# HEART_RATE.net
KiCad netlist of a schematic drawn in Altium Designer
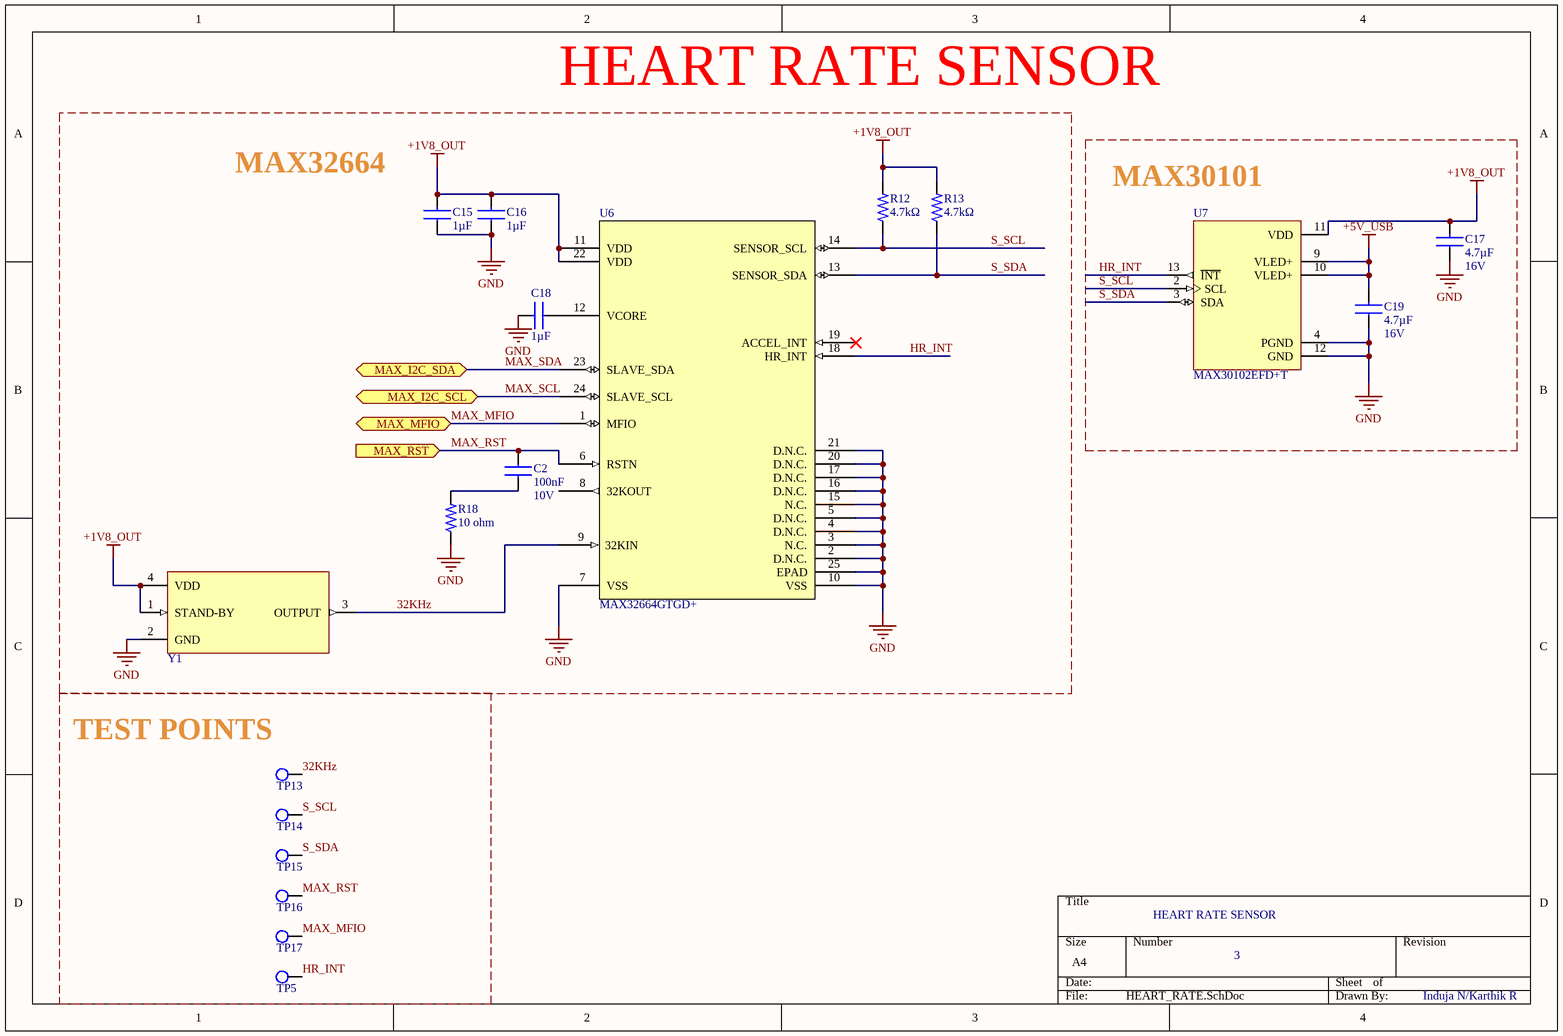
[diagram p0: HEART_RATE.SchDoc]

(export (version "E")
  (design (tool "Eeschema 10.0.6"))
  (components
    (comp (ref "C2")
      (value "100nF")
      (footprint "CAP_0603_1MM")
      (description "0603 0.1 uF 10 V ±10% Tolerance X7R SMT Multilayer Ceramic Chip Capacitor")
      (fields
        (field (name "MANUFACTURER") "Vishay")
        (field (name "MANUFACTURER PART NUMBER") "VJ0603Y104KXQCW1BC")
        (field (name "VOLTAGE RATING (DC)") "10V")
      )
      (libsource (lib "LPEDT_Components") (part "CAP 0.1uF 0603"))
    )
    (comp (ref "C15")
      (value "1µF")
      (footprint "Capacitor 0603")
      (description "16V 1uF X7R ±10% 0603 Multilayer Ceramic Capacitors MLCC - SMD/SMT ROHS")
      (fields
        (field (name "MANUFACTURER") "Samsung Electro-Mechanics")
        (field (name "MANUFACTURER PART NUMBER") "CL10B105KO8NNNC")
      )
      (libsource (lib "LPEDT_Components") (part "CAP 1uF 0603"))
    )
    (comp (ref "C16")
      (value "1µF")
      (footprint "Capacitor 0603")
      (description "16V 1uF X7R ±10% 0603 Multilayer Ceramic Capacitors MLCC - SMD/SMT ROHS")
      (fields
        (field (name "MANUFACTURER") "Samsung Electro-Mechanics")
        (field (name "MANUFACTURER PART NUMBER") "CL10B105KO8NNNC")
      )
      (libsource (lib "LPEDT_Components") (part "CAP 1uF 0603"))
    )
    (comp (ref "C17")
      (value "4.7µF")
      (footprint "Capacitor 0603")
      (description "16V 4.7uF X7R ±10% 0603 Multilayer Ceramic Capacitors MLCC - SMD/SMT ROHS")
      (fields
        (field (name "MANUFACTURER") "Murata")
        (field (name "MANUFACTURER PART NUMBER") "GRM188Z71C475KE21D")
        (field (name "VOLTAGE RATING (DC)") "16V")
      )
      (libsource (lib "LPEDT_Components") (part "CAP 4.7uF 16V X7R"))
    )
    (comp (ref "C18")
      (value "1µF")
      (footprint "Capacitor 0603")
      (description "16V 1uF X7R ±10% 0603 Multilayer Ceramic Capacitors MLCC - SMD/SMT ROHS")
      (fields
        (field (name "MANUFACTURER") "Samsung Electro-Mechanics")
        (field (name "MANUFACTURER PART NUMBER") "CL10B105KO8NNNC")
      )
      (libsource (lib "LPEDT_Components") (part "CAP 1uF 0603"))
    )
    (comp (ref "C19")
      (value "4.7µF")
      (footprint "Capacitor 0603")
      (description "16V 4.7uF X7R ±10% 0603 Multilayer Ceramic Capacitors MLCC - SMD/SMT ROHS")
      (fields
        (field (name "MANUFACTURER") "Murata")
        (field (name "MANUFACTURER PART NUMBER") "GRM188Z71C475KE21D")
        (field (name "VOLTAGE RATING (DC)") "16V")
      )
      (libsource (lib "LPEDT_Components") (part "CAP 4.7uF 16V X7R"))
    )
    (comp (ref "R12")
      (value "4.7kΩ")
      (footprint "RES_0603_1608X06")
      (fields
        (field (name "MANUFACTURER") "Yageo")
        (field (name "MANUFACTURER PART NUMBER") "RC0603FR-074K7L")
        (field (name "TOLERANCE") "1%")
      )
      (libsource (lib "LPEDT_Components") (part "RES 4.7K 0603"))
    )
    (comp (ref "R13")
      (value "4.7kΩ")
      (footprint "RES_0603_1608X06")
      (fields
        (field (name "MANUFACTURER") "Yageo")
        (field (name "MANUFACTURER PART NUMBER") "RC0603FR-074K7L")
        (field (name "TOLERANCE") "1%")
      )
      (libsource (lib "LPEDT_Components") (part "RES 4.7K 0603"))
    )
    (comp (ref "R18")
      (value "10 ohm")
      (footprint "RES_0603_1608X06")
      (description "10 Ohm CMP-2000-03846-1")
      (fields (field (name "PART NUMBER") "CRCW060310R0FKEAHP") (field (name "MANUFACTURER") "Vishay Dale"))
      (libsource (lib "LPEDT_Components") (part "RES 10 ohm"))
    )
    (comp (ref "TP5")
      (value "Test Point")
      (footprint "Test Point")
      (libsource (lib "LPEDT_Components") (part "Test Point"))
    )
    (comp (ref "TP13")
      (value "Test Point")
      (footprint "Test Point")
      (libsource (lib "LPEDT_Components") (part "Test Point"))
    )
    (comp (ref "TP14")
      (value "Test Point")
      (footprint "Test Point")
      (libsource (lib "LPEDT_Components") (part "Test Point"))
    )
    (comp (ref "TP15")
      (value "Test Point")
      (footprint "Test Point")
      (libsource (lib "LPEDT_Components") (part "Test Point"))
    )
    (comp (ref "TP16")
      (value "Test Point")
      (footprint "Test Point")
      (libsource (lib "LPEDT_Components") (part "Test Point"))
    )
    (comp (ref "TP17")
      (value "Test Point")
      (footprint "Test Point")
      (libsource (lib "LPEDT_Components") (part "Test Point"))
    )
    (comp (ref "U6")
      (value "MAX32664GTGD+")
      (footprint "21-100264_T2433+2C_MXM")
      (description "Ultra-Low Power Biometric Sensor Hub")
      (fields (field (name "COPYRIGHT") "Copyright (C) 2025 Ultra Librarian. All rights reserved."))
      (libsource (lib "LPEDT_Components") (part "MAX32664GTGD+"))
    )
    (comp (ref "U7")
      (value "MAX30102EFD+T")
      (footprint "XDCR_MAX30101EFD+")
      (description "SENSOR - OXIMETER/HEART RATE I2C")
      (fields
        (field (name "DIGI-KEY_PART_NUMBER") "MAX30102EFD+TTR-ND")
        (field (name "MF") "Maxim Integrated Products")
      )
      (libsource (lib "LPEDT_Components") (part "MAX30102EFD+T"))
    )
    (comp (ref "Y1")
      (value "ECS-327MV-DM-TR")
      (footprint "OSC_ECS-327MV-DM-TR-4")
      (description "32.768 kHz XO (Standard) CMOS Oscillator Enable/Disable 4-SMD, No Lead")
      (fields (field (name "MF") "ECS Inc.") (field (name "DIGI-KEY_PART_NUMBER") "50-ECS-327MV-DM-TR-ND"))
      (libsource (lib "LPEDT_Components") (part "32.768 kHz"))
    )
  )
  (nets
    (net (code "1") (name "+1V8_OUT") (class "Default")
      (node (ref "C15") (pin "1") (pinfunction "1_1") (pintype "passive"))
      (node (ref "C16") (pin "1") (pinfunction "1_1") (pintype "passive"))
      (node (ref "C17") (pin "1") (pinfunction "1_1") (pintype "passive"))
      (node (ref "R12") (pin "2") (pinfunction "2_2") (pintype "passive"))
      (node (ref "R13") (pin "2") (pinfunction "2_2") (pintype "passive"))
      (node (ref "U6") (pin "11") (pinfunction "VDD_11") (pintype "power_in"))
      (node (ref "U6") (pin "22") (pinfunction "VDD_22") (pintype "power_in"))
      (node (ref "U7") (pin "11") (pinfunction "VDD_11") (pintype "power_in"))
      (node (ref "Y1") (pin "1") (pinfunction "STAND-BY_1") (pintype "input"))
      (node (ref "Y1") (pin "4") (pinfunction "VDD_4") (pintype "power_in"))
    )
    (net (code "2") (name "+5V_USB") (class "Default")
      (node (ref "C19") (pin "1") (pinfunction "1_1") (pintype "passive"))
      (node (ref "U7") (pin "10") (pinfunction "VLED+_10") (pintype "power_in"))
      (node (ref "U7") (pin "9") (pinfunction "VLED+_9") (pintype "power_in"))
    )
    (net (code "3") (name "/32KHz") (class "Default")
      (node (ref "TP13") (pin "1") (pinfunction "1_1") (pintype "passive"))
      (node (ref "U6") (pin "9") (pinfunction "32KIN_9") (pintype "input"))
      (node (ref "Y1") (pin "3") (pinfunction "OUTPUT_3") (pintype "output"))
    )
    (net (code "4") (name "/HR_INT") (class "Default")
      (node (ref "TP5") (pin "1") (pinfunction "1_1") (pintype "passive"))
      (node (ref "U6") (pin "18") (pinfunction "HR_INT_18") (pintype "input"))
      (node (ref "U7") (pin "13") (pinfunction "~{INT}_13") (pintype "output"))
    )
    (net (code "5") (name "/MAX_MFIO") (class "Default")
      (node (ref "TP17") (pin "1") (pinfunction "1_1") (pintype "passive"))
      (node (ref "U6") (pin "1") (pinfunction "MFIO_1") (pintype "bidirectional"))
    )
    (net (code "6") (name "/MAX_RST") (class "Default")
      (node (ref "C2") (pin "1") (pinfunction "1_1") (pintype "passive"))
      (node (ref "TP16") (pin "1") (pinfunction "1_1") (pintype "passive"))
      (node (ref "U6") (pin "6") (pinfunction "RSTN_6") (pintype "input"))
    )
    (net (code "7") (name "/MAX_SCL") (class "Default")
      (node (ref "U6") (pin "24") (pinfunction "SLAVE_SCL_24") (pintype "bidirectional"))
    )
    (net (code "8") (name "/MAX_SDA") (class "Default")
      (node (ref "U6") (pin "23") (pinfunction "SLAVE_SDA_23") (pintype "bidirectional"))
    )
    (net (code "9") (name "/S_SCL") (class "Default")
      (node (ref "R12") (pin "1") (pinfunction "1_1") (pintype "passive"))
      (node (ref "TP14") (pin "1") (pinfunction "1_1") (pintype "passive"))
      (node (ref "U6") (pin "14") (pinfunction "SENSOR_SCL_14") (pintype "bidirectional"))
      (node (ref "U7") (pin "2") (pinfunction "SCL_2") (pintype "input"))
    )
    (net (code "10") (name "/S_SDA") (class "Default")
      (node (ref "R13") (pin "1") (pinfunction "1_1") (pintype "passive"))
      (node (ref "TP15") (pin "1") (pinfunction "1_1") (pintype "passive"))
      (node (ref "U6") (pin "13") (pinfunction "SENSOR_SDA_13") (pintype "bidirectional"))
      (node (ref "U7") (pin "3") (pinfunction "SDA_3") (pintype "bidirectional"))
    )
    (net (code "11") (name "GND") (class "Default")
      (node (ref "C15") (pin "2") (pinfunction "2_2") (pintype "passive"))
      (node (ref "C16") (pin "2") (pinfunction "2_2") (pintype "passive"))
      (node (ref "C17") (pin "2") (pinfunction "2_2") (pintype "passive"))
      (node (ref "C18") (pin "2") (pinfunction "2_2") (pintype "passive"))
      (node (ref "C19") (pin "2") (pinfunction "2_2") (pintype "passive"))
      (node (ref "R18") (pin "1") (pinfunction "1_1") (pintype "passive"))
      (node (ref "U6") (pin "10") (pinfunction "VSS_10") (pintype "power_in"))
      (node (ref "U6") (pin "15") (pinfunction "N.C._15") (pintype "passive"))
      (node (ref "U6") (pin "16") (pinfunction "D.N.C._16") (pintype "passive"))
      (node (ref "U6") (pin "17") (pinfunction "D.N.C._17") (pintype "passive"))
      (node (ref "U6") (pin "2") (pinfunction "D.N.C._2") (pintype "passive"))
      (node (ref "U6") (pin "20") (pinfunction "D.N.C._20") (pintype "passive"))
      (node (ref "U6") (pin "21") (pinfunction "D.N.C._21") (pintype "passive"))
      (node (ref "U6") (pin "25") (pinfunction "EPAD_25") (pintype "power_in"))
      (node (ref "U6") (pin "3") (pinfunction "N.C._3") (pintype "passive"))
      (node (ref "U6") (pin "4") (pinfunction "D.N.C._4") (pintype "passive"))
      (node (ref "U6") (pin "5") (pinfunction "D.N.C._5") (pintype "passive"))
      (node (ref "U6") (pin "7") (pinfunction "VSS_7") (pintype "power_in"))
      (node (ref "U7") (pin "12") (pinfunction "GND_12") (pintype "power_in"))
      (node (ref "U7") (pin "4") (pinfunction "PGND_4") (pintype "power_in"))
      (node (ref "Y1") (pin "2") (pinfunction "GND_2") (pintype "power_in"))
    )
    (net (code "12") (name "Net-(C2-Pad2)") (class "Default")
      (node (ref "C2") (pin "2") (pinfunction "2_2") (pintype "passive"))
      (node (ref "R18") (pin "2") (pinfunction "2_2") (pintype "passive"))
    )
    (net (code "13") (name "Net-(U6-VCORE)") (class "Default")
      (node (ref "C18") (pin "1") (pinfunction "1_1") (pintype "passive"))
      (node (ref "U6") (pin "12") (pinfunction "VCORE_12") (pintype "power_in"))
    )
    (net (code "14") (name "unconnected-(U6-32KOUT-Pad8)") (class "Default")
      (node (ref "U6") (pin "8") (pinfunction "32KOUT_8") (pintype "output"))
    )
    (net (code "15") (name "unconnected-(U6-ACCEL_INT-Pad19)") (class "Default")
      (node (ref "U6") (pin "19") (pinfunction "ACCEL_INT_19") (pintype "input+no_connect"))
    )
  )
)
